# Aux_kicker.net
KiCad netlist of a schematic drawn in EAGLE
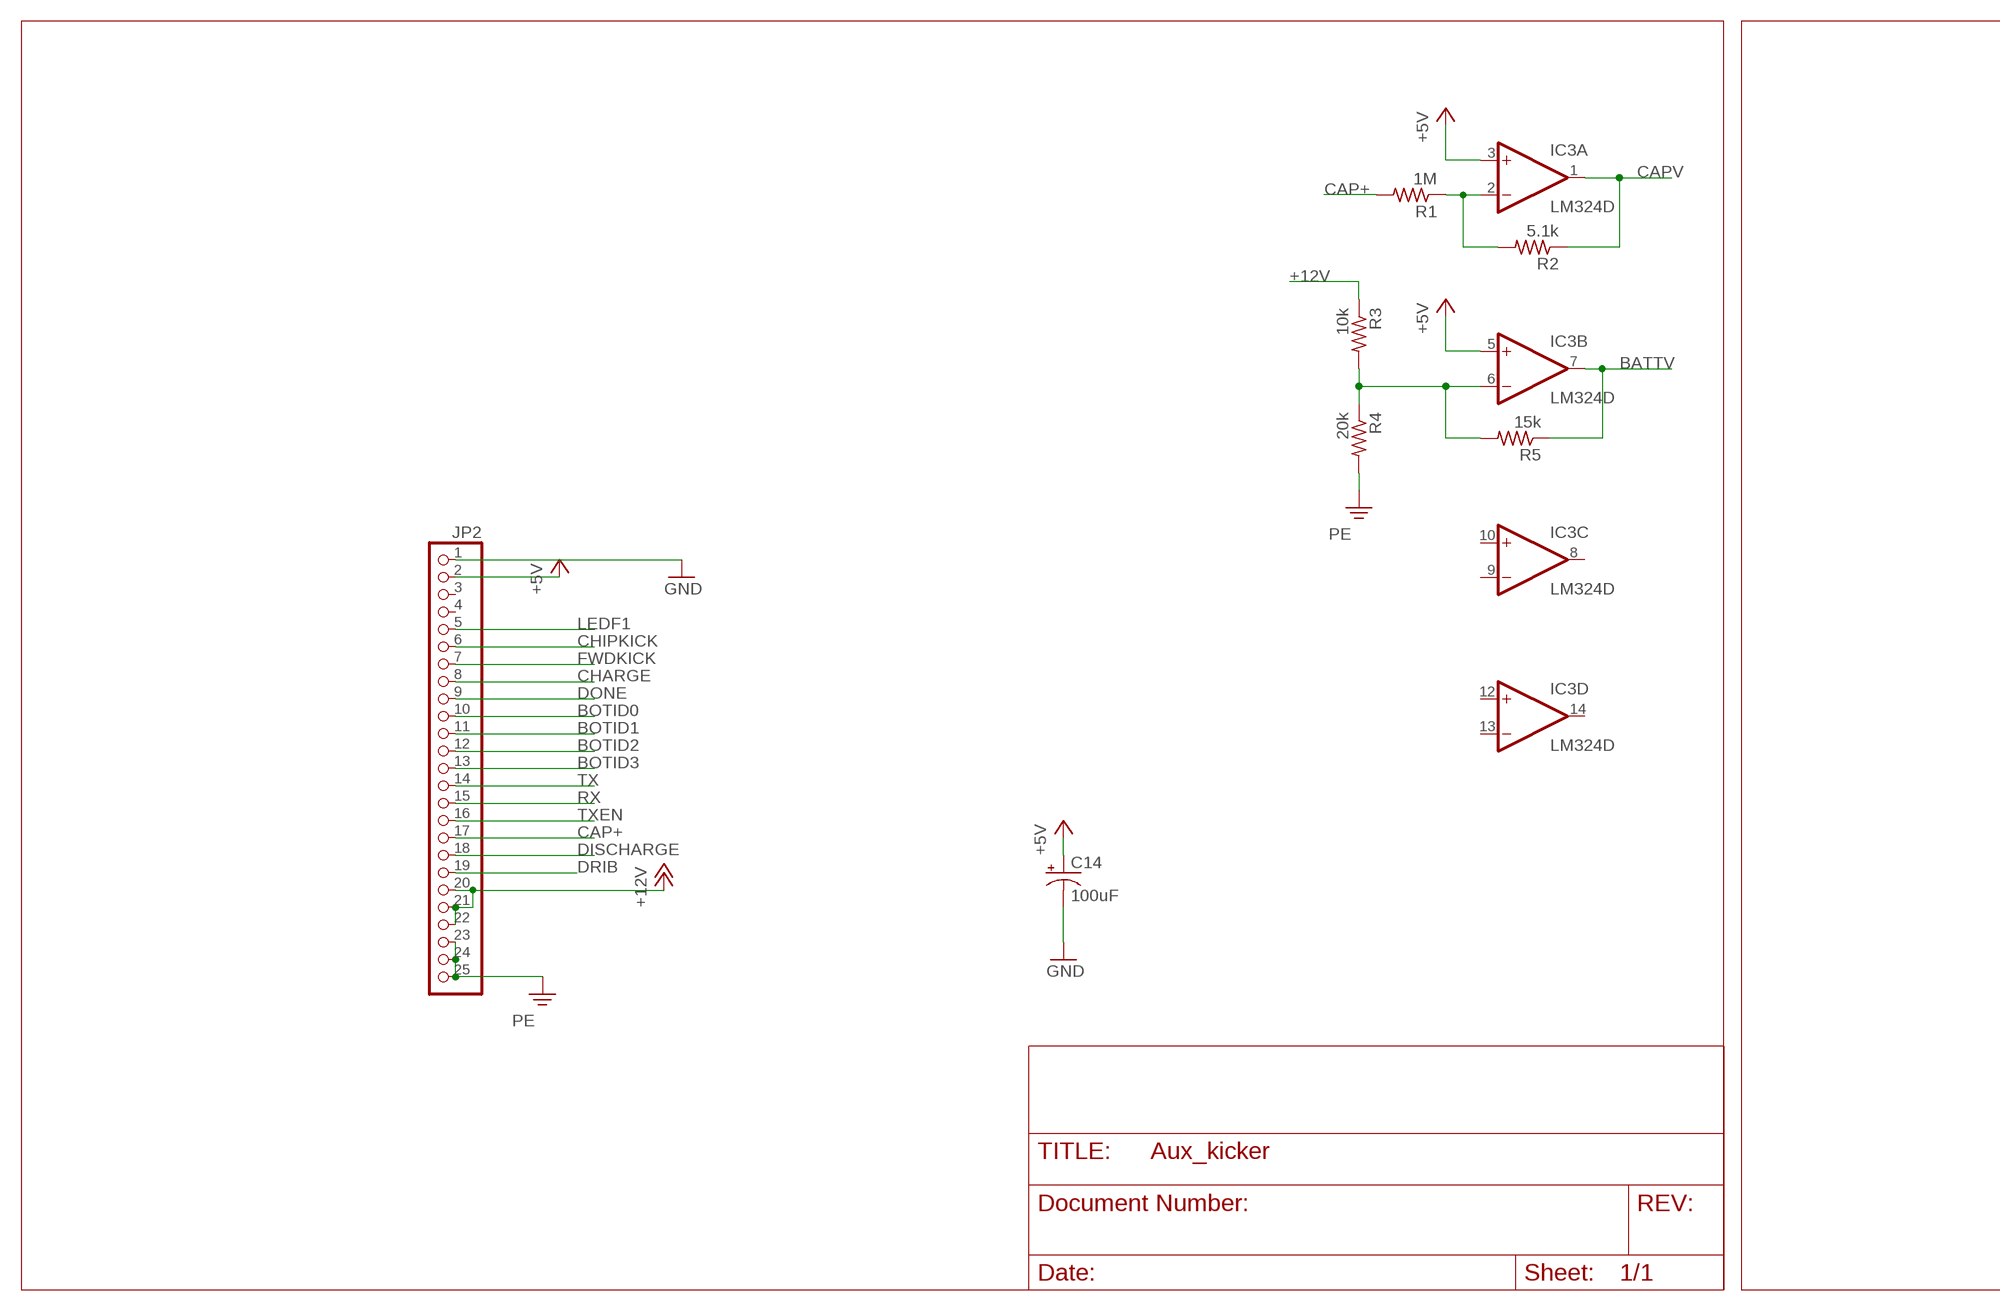
[diagram p0: schematic, sheet 1, part 1 of 2]
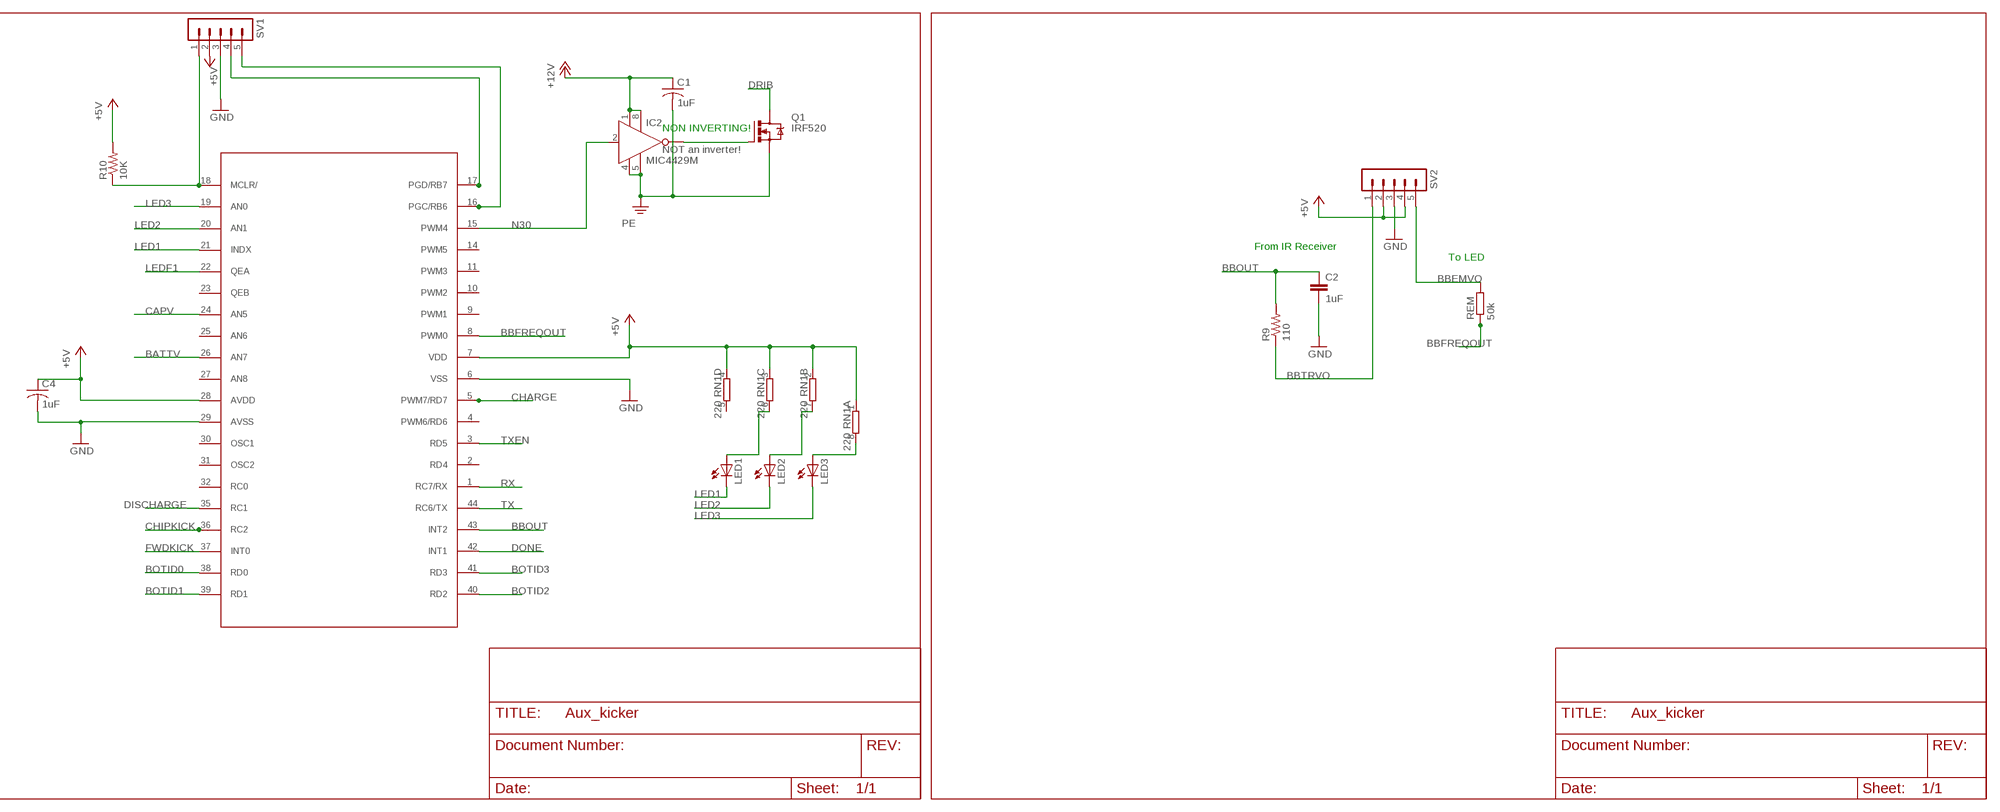
[diagram p1: schematic, sheet 1, part 2 of 2]

(export (version "E")
  (design (tool "Eeschema 10.0.6"))
  (components
    (comp (ref "C1")
      (value "1uF")
      (footprint "eagle-import:C0805")
      (libsource (lib "eagle-import") (part "C-USC0805"))
    )
    (comp (ref "C2")
      (value "1uF")
      (footprint "eagle-import:C0805")
      (libsource (lib "eagle-import") (part "C-EUC0805"))
    )
    (comp (ref "C4")
      (value "1uF")
      (footprint "eagle-import:C0805")
      (libsource (lib "eagle-import") (part "C-USC0805"))
    )
    (comp (ref "C14")
      (value "100uF")
      (footprint "eagle-import:E2,5-5")
      (libsource (lib "eagle-import") (part "CPOL-USE2.5-5"))
    )
    (comp (ref "IC1")
      (value "PIC18F4431S")
      (footprint "eagle-import:TQFP44")
      (libsource (lib "eagle-import") (part "PIC18F4431S"))
    )
    (comp (ref "IC2")
      (value "MIC4429M")
      (footprint "eagle-import:SO-08")
      (libsource (lib "eagle-import") (part "MIC4429M"))
    )
    (comp (ref "IC3")
      (value "LM324D")
      (footprint "eagle-import:SO14")
      (libsource (lib "eagle-import") (part "LM324D"))
    )
    (comp (ref "JP2")
      (value "PINHD-1X25")
      (footprint "eagle-import:1X25")
      (libsource (lib "eagle-import") (part "PINHD-1X25"))
    )
    (comp (ref "LED1")
      (value "LEDCHIPLED_0805")
      (footprint "eagle-import:CHIPLED_0805")
      (libsource (lib "eagle-import") (part "LEDCHIPLED_0805"))
    )
    (comp (ref "LED2")
      (value "LEDCHIPLED_0805")
      (footprint "eagle-import:CHIPLED_0805")
      (libsource (lib "eagle-import") (part "LEDCHIPLED_0805"))
    )
    (comp (ref "LED3")
      (value "LEDCHIPLED_0805")
      (footprint "eagle-import:CHIPLED_0805")
      (libsource (lib "eagle-import") (part "LEDCHIPLED_0805"))
    )
    (comp (ref "Q1")
      (value "IRF520")
      (footprint "eagle-import:TO220BV")
      (libsource (lib "eagle-import") (part "IRF520"))
    )
    (comp (ref "R1")
      (value "1M")
      (footprint "eagle-import:R0805")
      (libsource (lib "eagle-import") (part "R-US_R0805"))
    )
    (comp (ref "R2")
      (value "5.1k")
      (footprint "eagle-import:R0805")
      (libsource (lib "eagle-import") (part "R-US_R0805"))
    )
    (comp (ref "R3")
      (value "10k")
      (footprint "eagle-import:R0805")
      (libsource (lib "eagle-import") (part "R-US_R0805"))
    )
    (comp (ref "R4")
      (value "20k")
      (footprint "eagle-import:R0805")
      (libsource (lib "eagle-import") (part "R-US_R0805"))
    )
    (comp (ref "R5")
      (value "15k")
      (footprint "eagle-import:R0805")
      (libsource (lib "eagle-import") (part "R-US_R0805"))
    )
    (comp (ref "R9")
      (value "110")
      (footprint "eagle-import:R0805")
      (libsource (lib "eagle-import") (part "R-US_R0805"))
    )
    (comp (ref "R10")
      (value "10K")
      (footprint "eagle-import:R0805")
      (libsource (lib "eagle-import") (part "R-US_R0805"))
    )
    (comp (ref "REM")
      (value "50k")
      (footprint "eagle-import:R0805")
      (libsource (lib "eagle-import") (part "R-EU_R0805"))
    )
    (comp (ref "RN1")
      (value "220")
      (footprint "eagle-import:0603-ARC")
      (libsource (lib "eagle-import") (part "4R-N0603-ARC"))
    )
    (comp (ref "SV1")
      (value "MA05-1")
      (footprint "eagle-import:MA05-1")
      (libsource (lib "eagle-import") (part "MA05-1"))
    )
    (comp (ref "SV2")
      (value "MA05-1")
      (footprint "eagle-import:MA05-1")
      (libsource (lib "eagle-import") (part "MA05-1"))
    )
  )
  (nets
    (net (code "1") (name "+5V") (class "Default")
      (node (ref "C14") (pin "+") (pinfunction "+_+") (pintype "passive"))
      (node (ref "C4") (pin "1") (pinfunction "1_1") (pintype "passive"))
      (node (ref "IC1") (pin "28") (pinfunction "AVDD_28") (pintype "bidirectional"))
      (node (ref "IC1") (pin "7") (pinfunction "VDD_7") (pintype "bidirectional"))
      (node (ref "IC3") (pin "3") (pinfunction "+IN_3") (pintype "input"))
      (node (ref "IC3") (pin "5") (pinfunction "+IN_5") (pintype "input"))
      (node (ref "JP2") (pin "2") (pinfunction "2_2") (pintype "passive"))
      (node (ref "R10") (pin "2") (pinfunction "2_2") (pintype "passive"))
      (node (ref "RN1") (pin "1") (pinfunction "1_1") (pintype "passive"))
      (node (ref "RN1") (pin "2") (pinfunction "1_2") (pintype "passive"))
      (node (ref "RN1") (pin "3") (pinfunction "1_3") (pintype "passive"))
      (node (ref "RN1") (pin "4") (pinfunction "1_4") (pintype "passive"))
      (node (ref "SV1") (pin "2") (pinfunction "2_2") (pintype "passive"))
      (node (ref "SV2") (pin "2") (pinfunction "2_2") (pintype "passive"))
      (node (ref "SV2") (pin "4") (pinfunction "4_4") (pintype "passive"))
    )
    (net (code "2") (name "+12V") (class "Default")
      (node (ref "C1") (pin "1") (pinfunction "1_1") (pintype "passive"))
      (node (ref "IC2") (pin "1") (pinfunction "VS_1") (pintype "power_in"))
      (node (ref "IC2") (pin "8") (pinfunction "VS1_8") (pintype "power_in"))
      (node (ref "JP2") (pin "20") (pinfunction "20_20") (pintype "passive"))
      (node (ref "JP2") (pin "21") (pinfunction "21_21") (pintype "passive"))
      (node (ref "JP2") (pin "22") (pinfunction "22_22") (pintype "passive"))
      (node (ref "R3") (pin "1") (pinfunction "1_1") (pintype "passive"))
    )
    (net (code "3") (name "/BATTV") (class "Default")
      (node (ref "IC1") (pin "26") (pinfunction "AN7_26") (pintype "bidirectional"))
      (node (ref "IC3") (pin "7") (pinfunction "OUT_7") (pintype "output"))
      (node (ref "R5") (pin "1") (pinfunction "1_1") (pintype "passive"))
    )
    (net (code "4") (name "/BBEMVO") (class "Default")
      (node (ref "REM") (pin "2") (pinfunction "2_2") (pintype "passive"))
      (node (ref "SV2") (pin "5") (pinfunction "5_5") (pintype "passive"))
    )
    (net (code "5") (name "/BBFREQOUT") (class "Default")
      (node (ref "IC1") (pin "8") (pinfunction "PWM0_8") (pintype "bidirectional"))
      (node (ref "REM") (pin "1") (pinfunction "1_1") (pintype "passive"))
    )
    (net (code "6") (name "/BBOUT") (class "Default")
      (node (ref "C2") (pin "1") (pinfunction "1_1") (pintype "passive"))
      (node (ref "IC1") (pin "43") (pinfunction "INT2_43") (pintype "bidirectional"))
      (node (ref "R9") (pin "2") (pinfunction "2_2") (pintype "passive"))
    )
    (net (code "7") (name "/BBTRVO") (class "Default")
      (node (ref "R9") (pin "1") (pinfunction "1_1") (pintype "passive"))
      (node (ref "SV2") (pin "1") (pinfunction "1_1") (pintype "passive"))
    )
    (net (code "8") (name "/BOTID0") (class "Default")
      (node (ref "IC1") (pin "38") (pinfunction "RD0_38") (pintype "bidirectional"))
      (node (ref "JP2") (pin "10") (pinfunction "10_10") (pintype "passive"))
    )
    (net (code "9") (name "/BOTID1") (class "Default")
      (node (ref "IC1") (pin "39") (pinfunction "RD1_39") (pintype "bidirectional"))
      (node (ref "JP2") (pin "11") (pinfunction "11_11") (pintype "passive"))
    )
    (net (code "10") (name "/BOTID2") (class "Default")
      (node (ref "IC1") (pin "40") (pinfunction "RD2_40") (pintype "bidirectional"))
      (node (ref "JP2") (pin "12") (pinfunction "12_12") (pintype "passive"))
    )
    (net (code "11") (name "/BOTID3") (class "Default")
      (node (ref "IC1") (pin "41") (pinfunction "RD3_41") (pintype "bidirectional"))
      (node (ref "JP2") (pin "13") (pinfunction "13_13") (pintype "passive"))
    )
    (net (code "12") (name "/CAP+") (class "Default")
      (node (ref "JP2") (pin "17") (pinfunction "17_17") (pintype "passive"))
      (node (ref "R1") (pin "2") (pinfunction "2_2") (pintype "passive"))
    )
    (net (code "13") (name "/CAPV") (class "Default")
      (node (ref "IC1") (pin "24") (pinfunction "AN5_24") (pintype "bidirectional"))
      (node (ref "IC3") (pin "1") (pinfunction "OUT_1") (pintype "output"))
      (node (ref "R2") (pin "1") (pinfunction "1_1") (pintype "passive"))
    )
    (net (code "14") (name "/CHARGE") (class "Default")
      (node (ref "IC1") (pin "5") (pinfunction "PWM7/RD7_5") (pintype "bidirectional"))
      (node (ref "JP2") (pin "8") (pinfunction "8_8") (pintype "passive"))
    )
    (net (code "15") (name "/CHIPKICK") (class "Default")
      (node (ref "IC1") (pin "36") (pinfunction "RC2_36") (pintype "bidirectional"))
      (node (ref "JP2") (pin "6") (pinfunction "6_6") (pintype "passive"))
    )
    (net (code "16") (name "/DISCHARGE") (class "Default")
      (node (ref "IC1") (pin "35") (pinfunction "RC1_35") (pintype "bidirectional"))
      (node (ref "JP2") (pin "18") (pinfunction "18_18") (pintype "passive"))
    )
    (net (code "17") (name "/DONE") (class "Default")
      (node (ref "IC1") (pin "42") (pinfunction "INT1_42") (pintype "bidirectional"))
      (node (ref "JP2") (pin "9") (pinfunction "9_9") (pintype "passive"))
    )
    (net (code "18") (name "/DRIB") (class "Default")
      (node (ref "JP2") (pin "19") (pinfunction "19_19") (pintype "passive"))
      (node (ref "Q1") (pin "D") (pinfunction "D_D") (pintype "passive"))
    )
    (net (code "19") (name "/FWDKICK") (class "Default")
      (node (ref "IC1") (pin "37") (pinfunction "INT0_37") (pintype "bidirectional"))
      (node (ref "JP2") (pin "7") (pinfunction "7_7") (pintype "passive"))
    )
    (net (code "20") (name "/LED1") (class "Default")
      (node (ref "IC1") (pin "21") (pinfunction "INDX_21") (pintype "bidirectional"))
      (node (ref "LED1") (pin "C") (pinfunction "C_C") (pintype "passive"))
    )
    (net (code "21") (name "/LED2") (class "Default")
      (node (ref "IC1") (pin "20") (pinfunction "AN1_20") (pintype "bidirectional"))
      (node (ref "LED2") (pin "C") (pinfunction "C_C") (pintype "passive"))
    )
    (net (code "22") (name "/LED3") (class "Default")
      (node (ref "IC1") (pin "19") (pinfunction "AN0_19") (pintype "bidirectional"))
      (node (ref "LED3") (pin "C") (pinfunction "C_C") (pintype "passive"))
    )
    (net (code "23") (name "/LEDF1") (class "Default")
      (node (ref "IC1") (pin "22") (pinfunction "QEA_22") (pintype "bidirectional"))
      (node (ref "JP2") (pin "5") (pinfunction "5_5") (pintype "passive"))
    )
    (net (code "24") (name "/N30") (class "Default")
      (node (ref "IC1") (pin "15") (pinfunction "PWM4_15") (pintype "bidirectional"))
      (node (ref "IC2") (pin "2") (pinfunction "IN_2") (pintype "input"))
    )
    (net (code "25") (name "/RX") (class "Default")
      (node (ref "IC1") (pin "1") (pinfunction "RC7/RX_1") (pintype "bidirectional"))
      (node (ref "JP2") (pin "15") (pinfunction "15_15") (pintype "passive"))
    )
    (net (code "26") (name "/TX") (class "Default")
      (node (ref "IC1") (pin "44") (pinfunction "RC6/TX_44") (pintype "bidirectional"))
      (node (ref "JP2") (pin "14") (pinfunction "14_14") (pintype "passive"))
    )
    (net (code "27") (name "/TXEN") (class "Default")
      (node (ref "IC1") (pin "3") (pinfunction "RD5_3") (pintype "bidirectional"))
      (node (ref "JP2") (pin "16") (pinfunction "16_16") (pintype "passive"))
    )
    (net (code "28") (name "GND") (class "Default")
      (node (ref "C14") (pin "-") (pinfunction "-_-") (pintype "passive"))
      (node (ref "C2") (pin "2") (pinfunction "2_2") (pintype "passive"))
      (node (ref "C4") (pin "2") (pinfunction "2_2") (pintype "passive"))
      (node (ref "IC1") (pin "29") (pinfunction "AVSS_29") (pintype "bidirectional"))
      (node (ref "IC1") (pin "6") (pinfunction "VSS_6") (pintype "bidirectional"))
      (node (ref "JP2") (pin "1") (pinfunction "1_1") (pintype "passive"))
      (node (ref "SV1") (pin "3") (pinfunction "3_3") (pintype "passive"))
      (node (ref "SV2") (pin "3") (pinfunction "3_3") (pintype "passive"))
    )
    (net (code "29") (name "Net-(IC1-MCLR{slash})") (class "Default")
      (node (ref "IC1") (pin "18") (pinfunction "MCLR/_18") (pintype "bidirectional"))
      (node (ref "R10") (pin "1") (pinfunction "1_1") (pintype "passive"))
      (node (ref "SV1") (pin "1") (pinfunction "1_1") (pintype "passive"))
    )
    (net (code "30") (name "Net-(IC1-PGC{slash}RB6)") (class "Default")
      (node (ref "IC1") (pin "16") (pinfunction "PGC/RB6_16") (pintype "bidirectional"))
      (node (ref "SV1") (pin "5") (pinfunction "5_5") (pintype "passive"))
    )
    (net (code "31") (name "Net-(IC1-PGD{slash}RB7)") (class "Default")
      (node (ref "IC1") (pin "17") (pinfunction "PGD/RB7_17") (pintype "bidirectional"))
      (node (ref "SV1") (pin "4") (pinfunction "4_4") (pintype "passive"))
    )
    (net (code "32") (name "Net-(IC2-OUT-Pad6)") (class "Default")
      (node (ref "IC2") (pin "6") (pinfunction "OUT_6") (pintype "passive"))
      (node (ref "Q1") (pin "G") (pinfunction "G_G") (pintype "passive"))
    )
    (net (code "33") (name "Net-(IC3A--IN)") (class "Default")
      (node (ref "IC3") (pin "2") (pinfunction "-IN_2") (pintype "input"))
      (node (ref "R1") (pin "1") (pinfunction "1_1") (pintype "passive"))
      (node (ref "R2") (pin "2") (pinfunction "2_2") (pintype "passive"))
    )
    (net (code "34") (name "Net-(IC3B--IN)") (class "Default")
      (node (ref "IC3") (pin "6") (pinfunction "-IN_6") (pintype "input"))
      (node (ref "R3") (pin "2") (pinfunction "2_2") (pintype "passive"))
      (node (ref "R4") (pin "1") (pinfunction "1_1") (pintype "passive"))
      (node (ref "R5") (pin "2") (pinfunction "2_2") (pintype "passive"))
    )
    (net (code "35") (name "Net-(RN1A-2)") (class "Default")
      (node (ref "LED3") (pin "A") (pinfunction "A_A") (pintype "passive"))
      (node (ref "RN1") (pin "8") (pinfunction "2_8") (pintype "passive"))
    )
    (net (code "36") (name "Net-(RN1B-2)") (class "Default")
      (node (ref "LED2") (pin "A") (pinfunction "A_A") (pintype "passive"))
      (node (ref "RN1") (pin "7") (pinfunction "2_7") (pintype "passive"))
    )
    (net (code "37") (name "Net-(RN1C-2)") (class "Default")
      (node (ref "LED1") (pin "A") (pinfunction "A_A") (pintype "passive"))
      (node (ref "RN1") (pin "6") (pinfunction "2_6") (pintype "passive"))
    )
    (net (code "38") (name "PE") (class "Default")
      (node (ref "C1") (pin "2") (pinfunction "2_2") (pintype "passive"))
      (node (ref "IC2") (pin "4") (pinfunction "GND_4") (pintype "power_in"))
      (node (ref "IC2") (pin "5") (pinfunction "GND1_5") (pintype "power_in"))
      (node (ref "JP2") (pin "23") (pinfunction "23_23") (pintype "passive"))
      (node (ref "JP2") (pin "24") (pinfunction "24_24") (pintype "passive"))
      (node (ref "JP2") (pin "25") (pinfunction "25_25") (pintype "passive"))
      (node (ref "Q1") (pin "S") (pinfunction "S_S") (pintype "passive"))
      (node (ref "R4") (pin "2") (pinfunction "2_2") (pintype "passive"))
    )
    (net (code "39") (name "unconnected-(IC1-AN6-Pad25)") (class "Default")
      (node (ref "IC1") (pin "25") (pinfunction "AN6_25") (pintype "bidirectional"))
    )
    (net (code "40") (name "unconnected-(IC1-AN8-Pad27)") (class "Default")
      (node (ref "IC1") (pin "27") (pinfunction "AN8_27") (pintype "bidirectional"))
    )
    (net (code "41") (name "unconnected-(IC1-OSC1-Pad30)") (class "Default")
      (node (ref "IC1") (pin "30") (pinfunction "OSC1_30") (pintype "bidirectional"))
    )
    (net (code "42") (name "unconnected-(IC1-OSC2-Pad31)") (class "Default")
      (node (ref "IC1") (pin "31") (pinfunction "OSC2_31") (pintype "bidirectional"))
    )
    (net (code "43") (name "unconnected-(IC1-PWM1-Pad9)") (class "Default")
      (node (ref "IC1") (pin "9") (pinfunction "PWM1_9") (pintype "bidirectional"))
    )
    (net (code "44") (name "unconnected-(IC1-PWM2-Pad10)") (class "Default")
      (node (ref "IC1") (pin "10") (pinfunction "PWM2_10") (pintype "bidirectional"))
    )
    (net (code "45") (name "unconnected-(IC1-PWM3-Pad11)") (class "Default")
      (node (ref "IC1") (pin "11") (pinfunction "PWM3_11") (pintype "bidirectional"))
    )
    (net (code "46") (name "unconnected-(IC1-PWM5-Pad14)") (class "Default")
      (node (ref "IC1") (pin "14") (pinfunction "PWM5_14") (pintype "bidirectional"))
    )
    (net (code "47") (name "unconnected-(IC1-PWM6{slash}RD6-Pad4)") (class "Default")
      (node (ref "IC1") (pin "4") (pinfunction "PWM6/RD6_4") (pintype "bidirectional"))
    )
    (net (code "48") (name "unconnected-(IC1-QEB-Pad23)") (class "Default")
      (node (ref "IC1") (pin "23") (pinfunction "QEB_23") (pintype "bidirectional"))
    )
    (net (code "49") (name "unconnected-(IC1-RC0-Pad32)") (class "Default")
      (node (ref "IC1") (pin "32") (pinfunction "RC0_32") (pintype "bidirectional"))
    )
    (net (code "50") (name "unconnected-(IC1-RD4-Pad2)") (class "Default")
      (node (ref "IC1") (pin "2") (pinfunction "RD4_2") (pintype "bidirectional"))
    )
    (net (code "51") (name "unconnected-(IC2-OUT-Pad7)") (class "Default")
      (node (ref "IC2") (pin "7") (pinfunction "OUT_7") (pintype "passive"))
    )
    (net (code "52") (name "unconnected-(IC3C-+IN-Pad10)") (class "Default")
      (node (ref "IC3") (pin "10") (pinfunction "+IN_10") (pintype "input"))
    )
    (net (code "53") (name "unconnected-(IC3C--IN-Pad9)") (class "Default")
      (node (ref "IC3") (pin "9") (pinfunction "-IN_9") (pintype "input"))
    )
    (net (code "54") (name "unconnected-(IC3C-OUT-Pad8)") (class "Default")
      (node (ref "IC3") (pin "8") (pinfunction "OUT_8") (pintype "output"))
    )
    (net (code "55") (name "unconnected-(IC3D-+IN-Pad12)") (class "Default")
      (node (ref "IC3") (pin "12") (pinfunction "+IN_12") (pintype "input"))
    )
    (net (code "56") (name "unconnected-(IC3D--IN-Pad13)") (class "Default")
      (node (ref "IC3") (pin "13") (pinfunction "-IN_13") (pintype "input"))
    )
    (net (code "57") (name "unconnected-(IC3D-OUT-Pad14)") (class "Default")
      (node (ref "IC3") (pin "14") (pinfunction "OUT_14") (pintype "output"))
    )
    (net (code "58") (name "unconnected-(JP2-Pad3)") (class "Default")
      (node (ref "JP2") (pin "3") (pinfunction "3_3") (pintype "passive"))
    )
    (net (code "59") (name "unconnected-(JP2-Pad4)") (class "Default")
      (node (ref "JP2") (pin "4") (pinfunction "4_4") (pintype "passive"))
    )
    (net (code "60") (name "unconnected-(RN1D-2-Pad5)") (class "Default")
      (node (ref "RN1") (pin "5") (pinfunction "2_5") (pintype "passive"))
    )
  )
)
